# 555TimerBlink.net
KiCad netlist of a schematic drawn in EAGLE
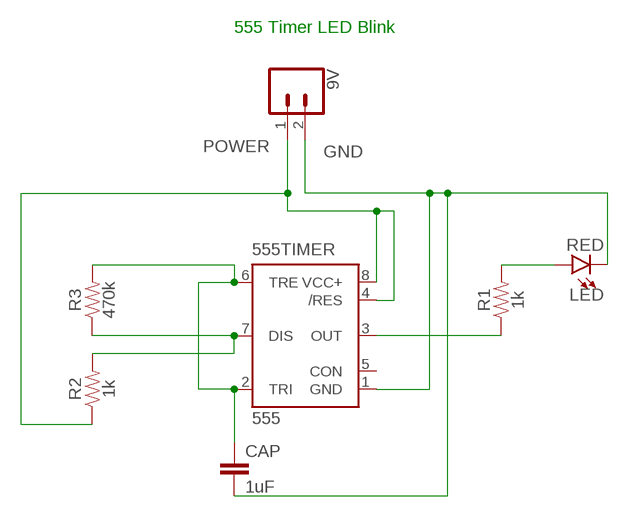
[diagram p0: schematic, sheet 1]

(export (version "E")
  (design (tool "Eeschema 10.0.6"))
  (components
    (comp (ref "9V")
      (value "CONN_02")
      (footprint "eagle-import:1X02")
      (libsource (lib "eagle-import") (part "CONN_02"))
    )
    (comp (ref "555TIMER")
      (value "555")
      (footprint "eagle-import:DIP08-KIT")
      (libsource (lib "eagle-import") (part "555KIT"))
    )
    (comp (ref "CAP")
      (value "1uF")
      (footprint "eagle-import:CAP-PTH-10MM")
      (libsource (lib "eagle-import") (part "10NF-PTH-10MM-10000V-1-%"))
    )
    (comp (ref "LED")
      (value "RED")
      (footprint "eagle-import:LED_3MM-NS")
      (libsource (lib "eagle-import") (part "LED-3MM-NO_SILK"))
    )
    (comp (ref "R1")
      (value "1k")
      (footprint "eagle-import:AXIAL-0.3")
      (libsource (lib "eagle-import") (part "1KOHM-HORIZ-1/4W-5%"))
    )
    (comp (ref "R2")
      (value "1k")
      (footprint "eagle-import:AXIAL-0.3")
      (libsource (lib "eagle-import") (part "1KOHM-HORIZ-1/4W-5%"))
    )
    (comp (ref "R3")
      (value "470k")
      (footprint "eagle-import:AXIAL-0.3")
      (libsource (lib "eagle-import") (part "1KOHM-HORIZ-1/4W-5%"))
    )
  )
  (nets
    (net (code "1") (name "/GND") (class "Default")
      (node (ref "555TIMER") (pin "1") (pinfunction "GND_1") (pintype "power_in"))
      (node (ref "9V") (pin "2") (pinfunction "2_2") (pintype "passive"))
      (node (ref "CAP") (pin "2") (pinfunction "2_2") (pintype "passive"))
      (node (ref "LED") (pin "K") (pinfunction "C_K") (pintype "passive"))
    )
    (net (code "2") (name "/POWER") (class "Default")
      (node (ref "555TIMER") (pin "4") (pinfunction "/RES_4") (pintype "input"))
      (node (ref "555TIMER") (pin "8") (pinfunction "VCC+_8") (pintype "power_in"))
      (node (ref "9V") (pin "1") (pinfunction "1_1") (pintype "passive"))
      (node (ref "R2") (pin "P$1") (pinfunction "1_P$1") (pintype "passive"))
    )
    (net (code "3") (name "Net-(555TIMER-DIS)") (class "Default")
      (node (ref "555TIMER") (pin "7") (pinfunction "DIS_7") (pintype "input"))
      (node (ref "R2") (pin "P$2") (pinfunction "2_P$2") (pintype "passive"))
      (node (ref "R3") (pin "P$1") (pinfunction "1_P$1") (pintype "passive"))
    )
    (net (code "4") (name "Net-(555TIMER-OUT)") (class "Default")
      (node (ref "555TIMER") (pin "3") (pinfunction "OUT_3") (pintype "output"))
      (node (ref "R1") (pin "P$1") (pinfunction "1_P$1") (pintype "passive"))
    )
    (net (code "5") (name "Net-(555TIMER-TRE)") (class "Default")
      (node (ref "555TIMER") (pin "2") (pinfunction "TRI_2") (pintype "input"))
      (node (ref "555TIMER") (pin "6") (pinfunction "TRE_6") (pintype "input"))
      (node (ref "CAP") (pin "1") (pinfunction "1_1") (pintype "passive"))
      (node (ref "R3") (pin "P$2") (pinfunction "2_P$2") (pintype "passive"))
    )
    (net (code "6") (name "Net-(R1-2)") (class "Default")
      (node (ref "LED") (pin "A") (pinfunction "A_A") (pintype "passive"))
      (node (ref "R1") (pin "P$2") (pinfunction "2_P$2") (pintype "passive"))
    )
    (net (code "7") (name "unconnected-(555TIMER-CON-Pad5)") (class "Default")
      (node (ref "555TIMER") (pin "5") (pinfunction "CON_5") (pintype "input"))
    )
  )
)
